# 1_V2.net
KiCad netlist of a schematic drawn in Altium Designer
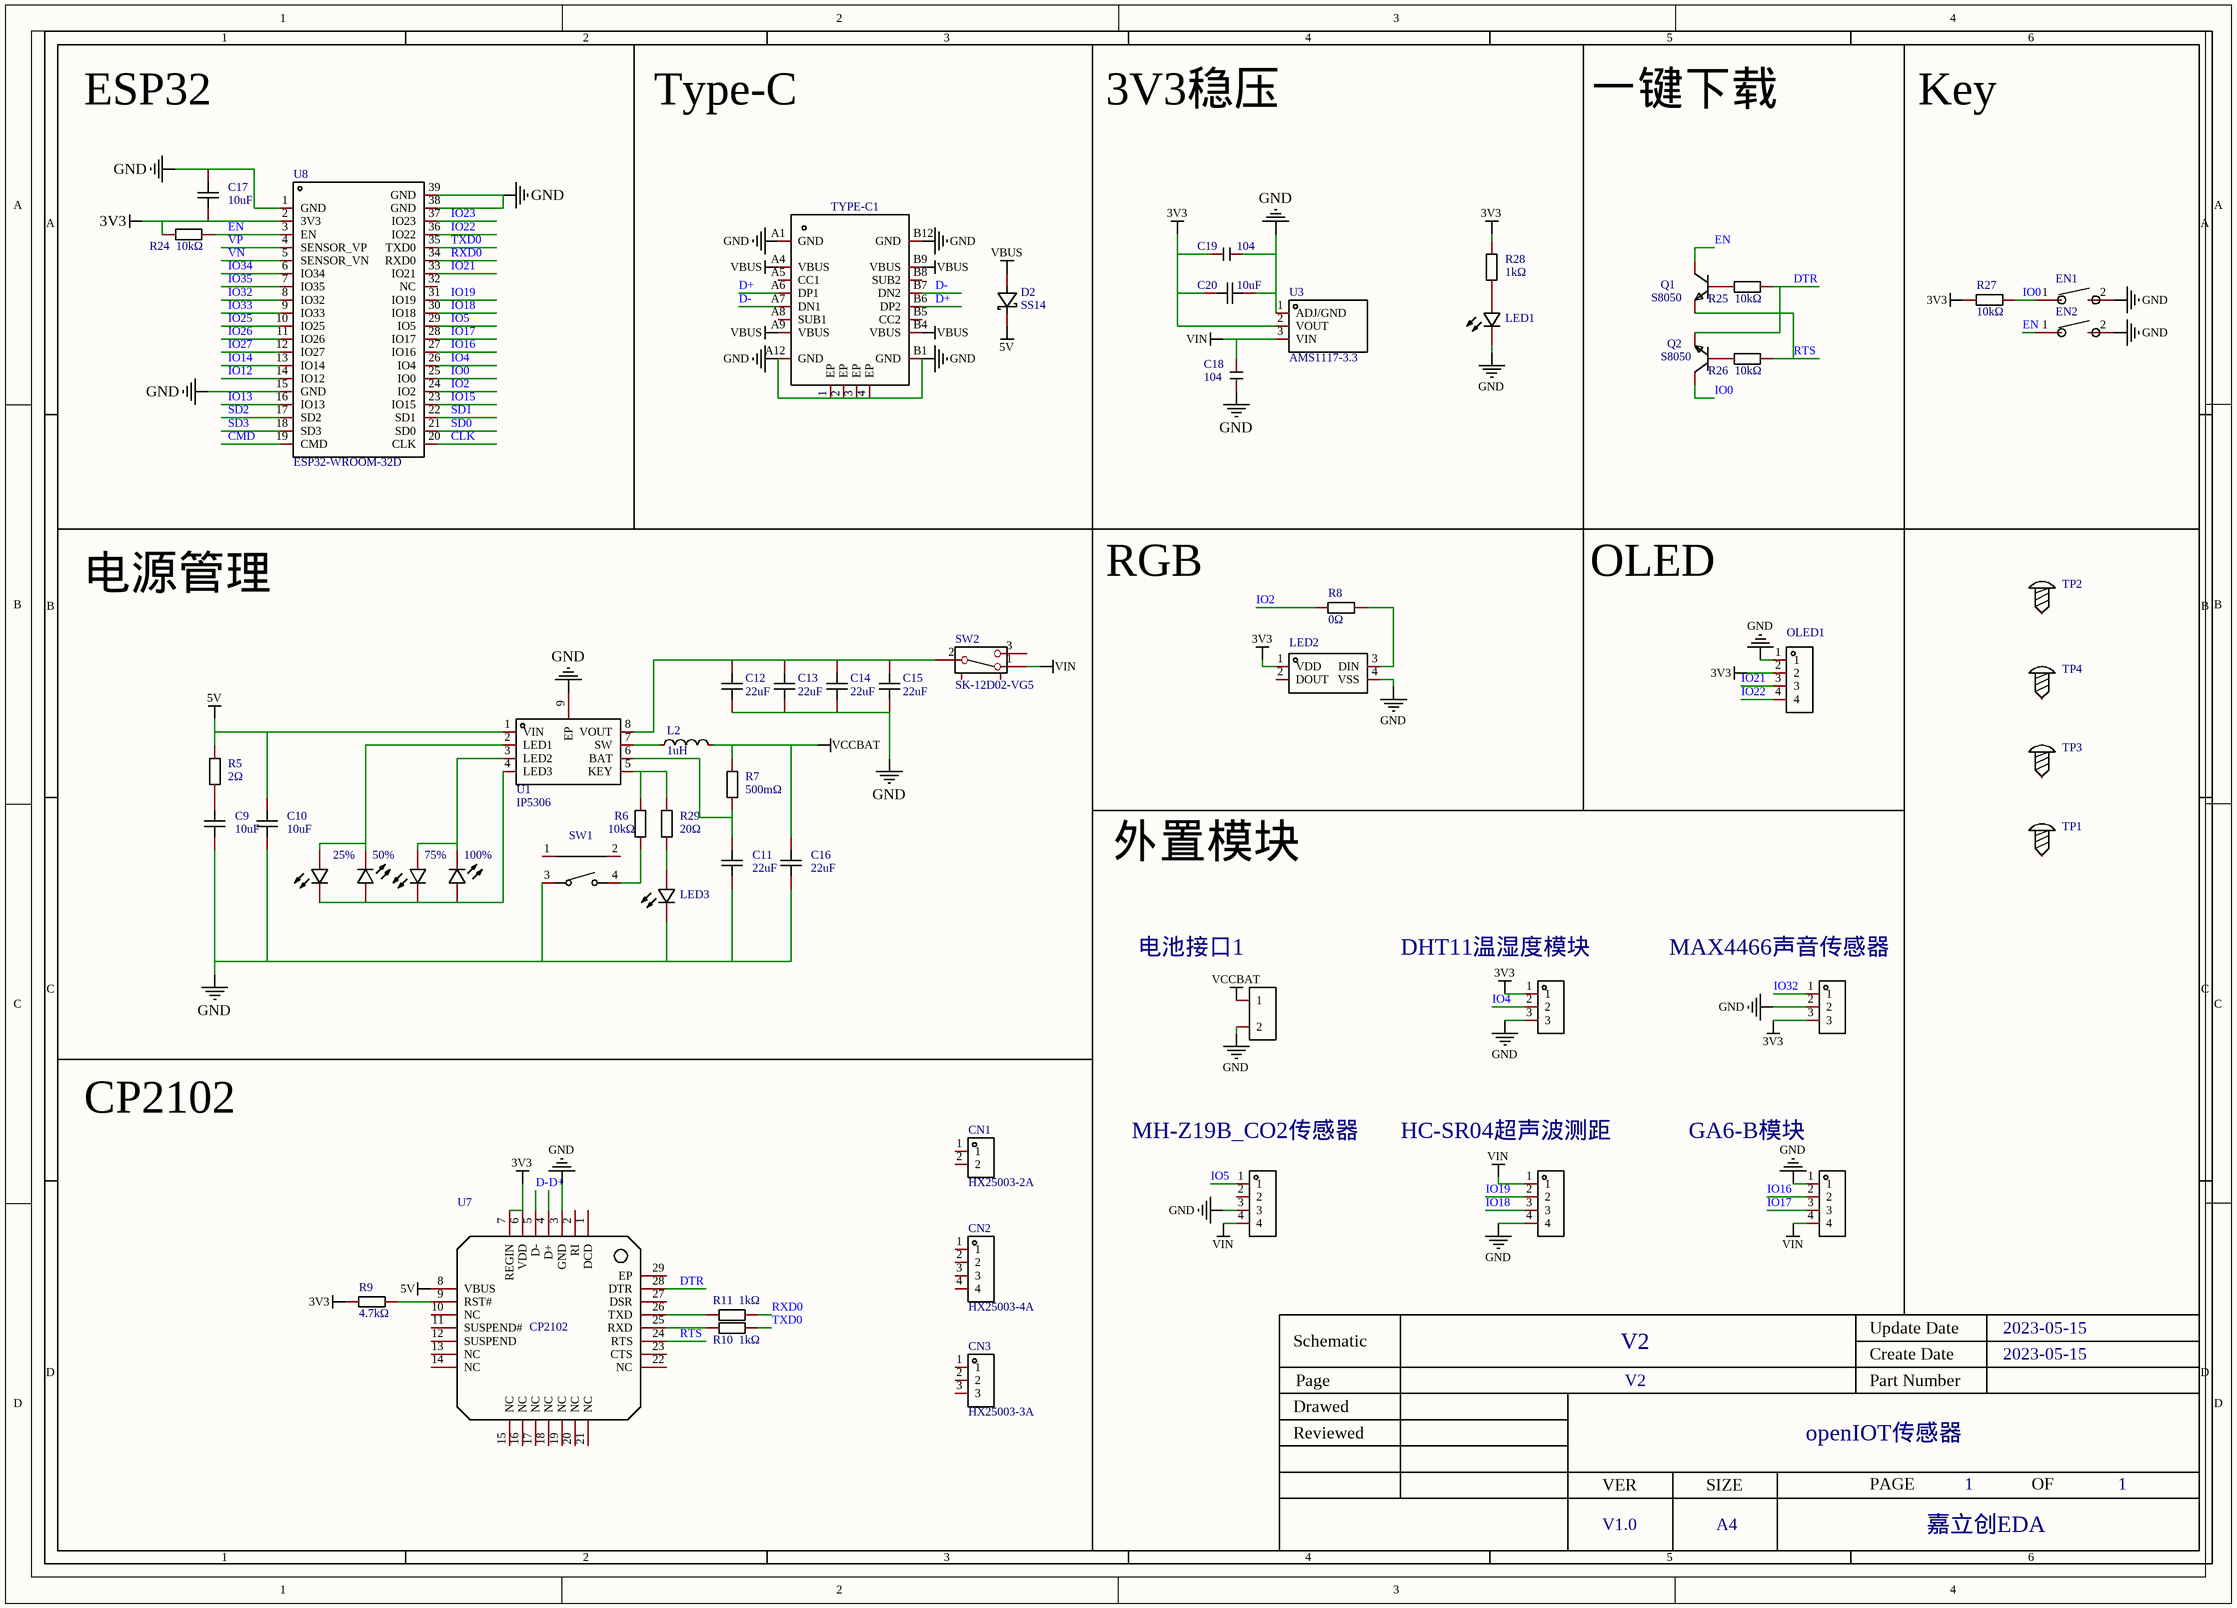
[diagram p0: 1_V2.schdoc]

(export (version "E")
  (design (tool "Eeschema 10.0.6"))
  (components
    (comp (ref "25%")
      (value "19-217/GHC-YR1S2/3T")
      (description "发光颜色:翠绿;二极管配置:-;主波长:520nm~535nm;色温:-;功率:110mW;安装方式:-;")
      (fields (field (name "MANUFACTURER") "EVERLIGHT(亿光)"))
      (libsource (lib "altium-import") (part "root_1_19-217/GHC-YR1S2/3T_"))
    )
    (comp (ref "50%")
      (value "19-217/GHC-YR1S2/3T")
      (description "发光颜色:翠绿;二极管配置:-;主波长:520nm~535nm;色温:-;功率:110mW;安装方式:-;")
      (fields (field (name "MANUFACTURER") "EVERLIGHT(亿光)"))
      (libsource (lib "altium-import") (part "root_3_19-217/GHC-YR1S2/3T_"))
    )
    (comp (ref "75%")
      (value "19-217/GHC-YR1S2/3T")
      (description "发光颜色:翠绿;二极管配置:-;主波长:520nm~535nm;色温:-;功率:110mW;安装方式:-;")
      (fields (field (name "MANUFACTURER") "EVERLIGHT(亿光)"))
      (libsource (lib "altium-import") (part "root_1_19-217/GHC-YR1S2/3T_"))
    )
    (comp (ref "100%")
      (value "19-217/GHC-YR1S2/3T")
      (description "发光颜色:翠绿;二极管配置:-;主波长:520nm~535nm;色温:-;功率:110mW;安装方式:-;")
      (fields (field (name "MANUFACTURER") "EVERLIGHT(亿光)"))
      (libsource (lib "altium-import") (part "root_3_19-217/GHC-YR1S2/3T_"))
    )
    (comp (ref "C9")
      (value "10uF")
      (description "容值:10uF;精度:±10%;额定电压:50V;材质(温度系数):X5R;")
      (fields
        (field (name "NAME") "10uF")
        (field (name "MANUFACTURER") "muRata(村田)")
        (field (name "MANUFACTURER PART") "GRM21BR61H106KE43L")
      )
      (libsource (lib "altium-import") (part "root_1_GRM21BR61H106KE43L_"))
    )
    (comp (ref "C10")
      (value "10uF")
      (description "容值:10uF;精度:±10%;额定电压:50V;材质(温度系数):X5R;")
      (fields
        (field (name "NAME") "10uF")
        (field (name "MANUFACTURER") "muRata(村田)")
        (field (name "MANUFACTURER PART") "GRM21BR61H106KE43L")
      )
      (libsource (lib "altium-import") (part "root_1_GRM21BR61H106KE43L_"))
    )
    (comp (ref "C11")
      (value "22uF")
      (description "容值:22uF;精度:±20%;额定电压:35V;材质(温度系数):X5R;")
      (fields
        (field (name "NAME") "22uF")
        (field (name "MANUFACTURER") "TDK")
        (field (name "MANUFACTURER PART") "C3216X5R1V226MTJ00E")
      )
      (libsource (lib "altium-import") (part "root_0_C3216X5R1V226MTJ00E_"))
    )
    (comp (ref "C12")
      (value "22uF")
      (description "容值:22uF;精度:±20%;额定电压:35V;材质(温度系数):X5R;")
      (fields
        (field (name "NAME") "22uF")
        (field (name "MANUFACTURER") "TDK")
        (field (name "MANUFACTURER PART") "C3216X5R1V226MTJ00E")
      )
      (libsource (lib "altium-import") (part "root_0_C3216X5R1V226MTJ00E_"))
    )
    (comp (ref "C13")
      (value "22uF")
      (description "容值:22uF;精度:±20%;额定电压:35V;材质(温度系数):X5R;")
      (fields
        (field (name "NAME") "22uF")
        (field (name "MANUFACTURER") "TDK")
        (field (name "MANUFACTURER PART") "C3216X5R1V226MTJ00E")
      )
      (libsource (lib "altium-import") (part "root_0_C3216X5R1V226MTJ00E_"))
    )
    (comp (ref "C14")
      (value "22uF")
      (description "容值:22uF;精度:±20%;额定电压:35V;材质(温度系数):X5R;")
      (fields
        (field (name "NAME") "22uF")
        (field (name "MANUFACTURER") "TDK")
        (field (name "MANUFACTURER PART") "C3216X5R1V226MTJ00E")
      )
      (libsource (lib "altium-import") (part "root_0_C3216X5R1V226MTJ00E_"))
    )
    (comp (ref "C15")
      (value "22uF")
      (description "容值:22uF;精度:±20%;额定电压:35V;材质(温度系数):X5R;")
      (fields
        (field (name "NAME") "22uF")
        (field (name "MANUFACTURER") "TDK")
        (field (name "MANUFACTURER PART") "C3216X5R1V226MTJ00E")
      )
      (libsource (lib "altium-import") (part "root_0_C3216X5R1V226MTJ00E_"))
    )
    (comp (ref "C16")
      (value "22uF")
      (description "容值:22uF;精度:±20%;额定电压:35V;材质(温度系数):X5R;")
      (fields
        (field (name "NAME") "22uF")
        (field (name "MANUFACTURER") "TDK")
        (field (name "MANUFACTURER PART") "C3216X5R1V226MTJ00E")
      )
      (libsource (lib "altium-import") (part "root_0_C3216X5R1V226MTJ00E_"))
    )
    (comp (ref "C17")
      (value "10uF")
      (description "容值:10uF;精度:±10%;额定电压:50V;材质(温度系数):X5R;")
      (fields
        (field (name "NAME") "10uF")
        (field (name "MANUFACTURER") "muRata(村田)")
        (field (name "MANUFACTURER PART") "GRM21BR61H106KE43L")
      )
      (libsource (lib "altium-import") (part "root_1_GRM21BR61H106KE43L_"))
    )
    (comp (ref "C18")
      (value "104")
      (fields (field (name "NAME") "104") (field (name "版权归属") "源创客"))
      (libsource (lib "altium-import") (part "root_1_104_"))
    )
    (comp (ref "C19")
      (value "104")
      (fields (field (name "NAME") "104") (field (name "版权归属") "源创客"))
      (libsource (lib "altium-import") (part "root_2_104_"))
    )
    (comp (ref "C20")
      (value "10uF")
      (description "容值:10uF;精度:±10%;额定电压:50V;材质(温度系数):X5R;")
      (fields
        (field (name "NAME") "10uF")
        (field (name "MANUFACTURER") "muRata(村田)")
        (field (name "MANUFACTURER PART") "GRM21BR61H106KE43L")
      )
      (libsource (lib "altium-import") (part "root_2_GRM21BR61H106KE43L_"))
    )
    (comp (ref "CN1")
      (value "HX25003-2A")
      (description "参考系列:XH;间距:2.5mm;插针结构:1x2P;排数:1;每排PIN数:2;行距:-;公母:公型插针;安装方式:直插;额定电流:-;工作温度范围:-;")
      (fields (field (name "NAME") "HX25003-2A") (field (name "MANUFACTURER") "HX(红星)"))
      (libsource (lib "altium-import") (part "root_0_HX25003-2A_"))
    )
    (comp (ref "CN2")
      (value "HX25003-4A")
      (description "参考系列:XH;间距:2.5mm;插针结构:1x4P;排数:1;每排PIN数:4;行距:-;公母:公型插针;安装方式:直插;额定电流:-;工作温度范围:-;")
      (fields (field (name "NAME") "HX25003-4A") (field (name "MANUFACTURER") "HX(红星)"))
      (libsource (lib "altium-import") (part "root_0_HX25003-4A_"))
    )
    (comp (ref "CN3")
      (value "HX25003-3A")
      (description "参考系列:XH;间距:2.5mm;插针结构:1x3P;排数:1;每排PIN数:3;行距:-;公母:公型插针;安装方式:直插;额定电流:-;工作温度范围:-;")
      (fields (field (name "NAME") "HX25003-3A") (field (name "MANUFACTURER") "HX(红星)"))
      (libsource (lib "altium-import") (part "root_0_HX25003-3A_"))
    )
    (comp (ref "D2")
      (value "SS14")
      (description "二极管配置:-;直流反向耐压(Vr):40V;平均整流电流(Io):1A;正向压降(Vf):550mV@1A;反向电流(Ir):500uA@40V;")
      (fields (field (name "NAME") "SS14") (field (name "MANUFACTURER") "KUU"))
      (libsource (lib "altium-import") (part "root_1_SS14_C2909920_"))
    )
    (comp (ref "DHT11温湿度模块")
      (value "B-2200S03P-A120")
      (description "排数:单排;总孔位数:3;间距:2.54mm;插孔结构:1x3P;行距:-;安装类型:直插;塑高:-;触头材质:黄铜;触头镀层:-;")
      (fields (field (name "MANUFACTURER") "Ckmtw(灿科盟)"))
      (libsource (lib "altium-import") (part "root_0_B-2200S03P-A120_"))
    )
    (comp (ref "EN1")
      (value "TSA343G00-250J2")
      (fields (field (name "MANUFACTURER") "BRIGHT(博瑞泰)"))
      (libsource (lib "altium-import") (part "root_0_TSA343G00-250J2_"))
    )
    (comp (ref "EN2")
      (value "TSA343G00-250J2")
      (fields (field (name "MANUFACTURER") "BRIGHT(博瑞泰)"))
      (libsource (lib "altium-import") (part "root_0_TSA343G00-250J2_"))
    )
    (comp (ref "GA6-B模块")
      (value "2.54-1*4P母")
      (fields (field (name "MANUFACTURER") "BOOMELE(博穆精密)"))
      (libsource (lib "altium-import") (part "root_0_2.54-1*4P母_"))
    )
    (comp (ref "HC-SR04超声波测距")
      (value "2.54-1*4P母")
      (fields (field (name "MANUFACTURER") "BOOMELE(博穆精密)"))
      (libsource (lib "altium-import") (part "root_0_2.54-1*4P母_"))
    )
    (comp (ref "L2")
      (value "1uH")
      (description "电感值:1uH;精度:±20%;额定电流:8.5A;饱和电流(Isat):14A;")
      (fields
        (field (name "NAME") "1uH")
        (field (name "MANUFACTURER") "cjiang(长江微电)")
        (field (name "MANUFACTURER PART") "FXL0618-1R0-M")
      )
      (libsource (lib "altium-import") (part "root_0_FXL0618-1R0-M_"))
    )
    (comp (ref "LED1")
      (value "19-217/GHC-YR1S2/3T")
      (description "发光颜色:翠绿;二极管配置:-;主波长:520nm~535nm;色温:-;功率:110mW;安装方式:-;")
      (fields (field (name "MANUFACTURER") "EVERLIGHT(亿光)"))
      (libsource (lib "altium-import") (part "root_1_19-217/GHC-YR1S2/3T_"))
    )
    (comp (ref "LED2")
      (value "WS2812B-V5/W")
      (fields (field (name "MANUFACTURER") "worldsemi"))
      (libsource (lib "altium-import") (part "root_0_WS2812B-V5/W_"))
    )
    (comp (ref "LED3")
      (value "19-217/GHC-YR1S2/3T")
      (description "发光颜色:翠绿;二极管配置:-;主波长:520nm~535nm;色温:-;功率:110mW;安装方式:-;")
      (fields (field (name "MANUFACTURER") "EVERLIGHT(亿光)"))
      (libsource (lib "altium-import") (part "root_1_19-217/GHC-YR1S2/3T_"))
    )
    (comp (ref "MAX4466声音传感器")
      (value "B-2200S03P-A120")
      (description "排数:单排;总孔位数:3;间距:2.54mm;插孔结构:1x3P;行距:-;安装类型:直插;塑高:-;触头材质:黄铜;触头镀层:-;")
      (fields (field (name "MANUFACTURER") "Ckmtw(灿科盟)"))
      (libsource (lib "altium-import") (part "root_0_B-2200S03P-A120_"))
    )
    (comp (ref "MH-Z19B_CO2传感器")
      (value "2.54-1*4P母")
      (fields (field (name "MANUFACTURER") "BOOMELE(博穆精密)"))
      (libsource (lib "altium-import") (part "root_0_2.54-1*4P母_"))
    )
    (comp (ref "OLED1")
      (value "2.54-1*4P母")
      (fields (field (name "MANUFACTURER") "BOOMELE(博穆精密)"))
      (libsource (lib "altium-import") (part "root_0_2.54-1*4P母_"))
    )
    (comp (ref "Q1")
      (value "S8050")
      (fields (field (name "NAME") "S8050") (field (name "MANUFACTURER") "WPMtek(维攀微)"))
      (libsource (lib "altium-import") (part "root_0_S8050_"))
    )
    (comp (ref "Q2")
      (value "S8050")
      (fields (field (name "NAME") "S8050") (field (name "MANUFACTURER") "WPMtek(维攀微)"))
      (libsource (lib "altium-import") (part "root_2_S8050_"))
    )
    (comp (ref "R5")
      (value "2Ω")
      (description "电阻类型:厚膜电阻;阻值:2Ω;精度:±1%;功率:125mW;")
      (fields
        (field (name "NAME") "2Ω")
        (field (name "MANUFACTURER") "UNI-ROYAL(厚声)")
        (field (name "MANUFACTURER PART") "0805W8F200KT5E")
      )
      (libsource (lib "altium-import") (part "root_1_0805W8F200KT5E_"))
    )
    (comp (ref "R6")
      (value "10kΩ")
      (description "电阻类型:厚膜电阻;阻值:10kΩ;精度:±1%;功率:125mW;")
      (fields
        (field (name "NAME") "10kΩ")
        (field (name "MANUFACTURER") "UNI-ROYAL(厚声)")
        (field (name "MANUFACTURER PART") "0805W8F1002T5E")
      )
      (libsource (lib "altium-import") (part "root_1_0805W8F1002T5E_C17414_"))
    )
    (comp (ref "R7")
      (value "500mΩ")
      (description "电阻类型:厚膜电阻;阻值:500mΩ;精度:±1%;功率:250mW;")
      (fields
        (field (name "NAME") "500mΩ")
        (field (name "MANUFACTURER") "UNI-ROYAL(厚声)")
        (field (name "MANUFACTURER PART") "1206W4F500LT5E")
      )
      (libsource (lib "altium-import") (part "root_1_1206W4F500LT5E_"))
    )
    (comp (ref "R8")
      (value "0Ω")
      (description "电阻类型:厚膜电阻;阻值:0Ω;精度:±1%;功率:100mW;最大工作电压:75V;工作温度范围:-55℃~+155℃;")
      (fields
        (field (name "MANUFACTURER") "UNI-ROYAL(厚声)")
        (field (name "MANUFACTURER PART") "0603WAF0000T5E")
      )
      (libsource (lib "altium-import") (part "root_2_0603WAF0000T5E_"))
    )
    (comp (ref "R9")
      (value "4.7kΩ")
      (description "电阻类型:厚膜电阻;阻值:4.7kΩ;精度:±1%;功率:100mW;")
      (fields
        (field (name "NAME") "4.7kΩ")
        (field (name "MANUFACTURER") "UNI-ROYAL(厚声)")
        (field (name "MANUFACTURER PART") "0603WAF4701T5E")
      )
      (libsource (lib "altium-import") (part "root_0_0603WAF4701T5E_"))
    )
    (comp (ref "R10")
      (value "1kΩ")
      (description "电阻类型:厚膜电阻;阻值:1kΩ;精度:±1%;功率:100mW;")
      (fields
        (field (name "NAME") "1kΩ")
        (field (name "MANUFACTURER") "UNI-ROYAL(厚声)")
        (field (name "MANUFACTURER PART") "0603WAF1001T5E")
      )
      (libsource (lib "altium-import") (part "root_0_0603WAF1001T5E_"))
    )
    (comp (ref "R11")
      (value "1kΩ")
      (description "电阻类型:厚膜电阻;阻值:1kΩ;精度:±1%;功率:100mW;")
      (fields
        (field (name "NAME") "1kΩ")
        (field (name "MANUFACTURER") "UNI-ROYAL(厚声)")
        (field (name "MANUFACTURER PART") "0603WAF1001T5E")
      )
      (libsource (lib "altium-import") (part "root_0_0603WAF1001T5E_"))
    )
    (comp (ref "R24")
      (value "10kΩ")
      (description "电阻类型:厚膜电阻;阻值:10kΩ;精度:±1%;功率:100mW;")
      (fields
        (field (name "NAME") "10kΩ")
        (field (name "MANUFACTURER") "UNI-ROYAL(厚声)")
        (field (name "MANUFACTURER PART") "0603WAF1002T5E")
      )
      (libsource (lib "altium-import") (part "root_0_0603WAF1002T5E_"))
    )
    (comp (ref "R25")
      (value "10kΩ")
      (description "电阻类型:厚膜电阻;阻值:10kΩ;精度:±1%;功率:100mW;")
      (fields
        (field (name "NAME") "10kΩ")
        (field (name "MANUFACTURER") "UNI-ROYAL(厚声)")
        (field (name "MANUFACTURER PART") "0603WAF1002T5E")
      )
      (libsource (lib "altium-import") (part "root_0_0603WAF1002T5E_"))
    )
    (comp (ref "R26")
      (value "10kΩ")
      (description "电阻类型:厚膜电阻;阻值:10kΩ;精度:±1%;功率:100mW;")
      (fields
        (field (name "NAME") "10kΩ")
        (field (name "MANUFACTURER") "UNI-ROYAL(厚声)")
        (field (name "MANUFACTURER PART") "0603WAF1002T5E")
      )
      (libsource (lib "altium-import") (part "root_0_0603WAF1002T5E_"))
    )
    (comp (ref "R27")
      (value "10kΩ")
      (description "电阻类型:厚膜电阻;阻值:10kΩ;精度:±1%;功率:100mW;")
      (fields
        (field (name "NAME") "10kΩ")
        (field (name "MANUFACTURER") "UNI-ROYAL(厚声)")
        (field (name "MANUFACTURER PART") "0603WAF1002T5E")
      )
      (libsource (lib "altium-import") (part "root_2_0603WAF1002T5E_"))
    )
    (comp (ref "R28")
      (value "1kΩ")
      (description "电阻类型:厚膜电阻;阻值:1kΩ;精度:±1%;功率:100mW;")
      (fields
        (field (name "NAME") "1kΩ")
        (field (name "MANUFACTURER") "UNI-ROYAL(厚声)")
        (field (name "MANUFACTURER PART") "0603WAF1001T5E")
      )
      (libsource (lib "altium-import") (part "root_1_0603WAF1001T5E_"))
    )
    (comp (ref "R29")
      (value "20Ω")
      (description "电阻类型:厚膜电阻;阻值:20Ω;精度:±1%;功率:100mW;")
      (fields
        (field (name "NAME") "20Ω")
        (field (name "MANUFACTURER") "UNI-ROYAL(厚声)")
        (field (name "MANUFACTURER PART") "0603WAF200JT5E")
      )
      (libsource (lib "altium-import") (part "root_1_0603WAF200JT5E_"))
    )
    (comp (ref "SW1")
      (value "TS24CA")
      (description "触点电流:50mA;额定电压(DC):12V;电路结构:单刀单掷;安装方式:卧贴;带灯:-;机械寿命:-;")
      (fields (field (name "MANUFACTURER") "SHOU HAN(首韩)"))
      (libsource (lib "altium-import") (part "root_0_TS24CA_"))
    )
    (comp (ref "SW2")
      (value "SK-12D02-VG5")
      (fields (field (name "NAME") "SK-12D02-VG5") (field (name "MANUFACTURER") "韩国韩荣"))
      (libsource (lib "altium-import") (part "root_0_SK-12D02-VG5_C136722_"))
    )
    (comp (ref "TP1") (value "M2螺丝") (libsource (lib "altium-import") (part "root_0_M2螺丝_")))
    (comp (ref "TP2") (value "M2螺丝") (libsource (lib "altium-import") (part "root_0_M2螺丝_")))
    (comp (ref "TP3") (value "M2螺丝") (libsource (lib "altium-import") (part "root_0_M2螺丝_")))
    (comp (ref "TP4") (value "M2螺丝") (libsource (lib "altium-import") (part "root_0_M2螺丝_")))
    (comp (ref "TYPE-C1")
      (value "KH-TYPE-C-16P")
      (description "连接器类型:Type-C;标准:-;公母:母座;触点数量:16;端口数量:1;安装方式:卧贴;额定电流 - 电源:3A;工作温度范围:-40℃~+85℃;")
      (fields (field (name "MANUFACTURER") "kinghelm(金航标)"))
      (libsource (lib "altium-import") (part "root_0_KH-TYPE-C-16P_"))
    )
    (comp (ref "U1")
      (value "IP5306")
      (description "2.1A充电2.4A放电高集成度移动电源SOC")
      (fields (field (name "NAME") "IP5306") (field (name "MANUFACTURER") "INJOINIC(英集芯)"))
      (libsource (lib "altium-import") (part "root_0_IP5306_"))
    )
    (comp (ref "U3")
      (value "AMS1117-3.3")
      (description "输出类型:-;")
      (fields (field (name "NAME") "AMS1117-3.3") (field (name "MANUFACTURER") "Slkor(萨科微)"))
      (libsource (lib "altium-import") (part "root_0_AMS1117-3.3_C880752_"))
    )
    (comp (ref "U7")
      (value "CP2102")
      (description "类型:Transceiver;协议类别:USB;驱动器/接收器数:1/1;数据速率:1Mbps;")
      (fields (field (name "NAME") "CP2102") (field (name "MANUFACTURER") "SILICON LABS(芯科)"))
      (libsource (lib "altium-import") (part "root_3_CP2102-GMR_"))
    )
    (comp (ref "U8")
      (value "ESP32-WROOM-32D")
      (fields (field (name "NAME") "ESP32-WROOM-32D"))
      (libsource (lib "altium-import") (part "root_0_ESP32-WROOM-32D_"))
    )
    (comp (ref "电池接口1")
      (value "826629-2")
      (fields (field (name "MANUFACTURER") "TE Connectivity(美国泰科)"))
      (libsource (lib "altium-import") (part "root_0_826629-2_"))
    )
  )
  (nets
    (net (code "1") (name "/CLK") (class "Default")
      (node (ref "U8") (pin "20") (pinfunction "CLK_20") (pintype "passive"))
    )
    (net (code "2") (name "/CMD") (class "Default")
      (node (ref "U8") (pin "19") (pinfunction "CMD_19") (pintype "passive"))
    )
    (net (code "3") (name "/D+") (class "Default")
      (node (ref "TYPE-C1") (pin "A6") (pinfunction "DP1_A6") (pintype "passive"))
      (node (ref "TYPE-C1") (pin "B6") (pinfunction "DP2_B6") (pintype "passive"))
      (node (ref "U7") (pin "4") (pinfunction "D+_4") (pintype "passive"))
    )
    (net (code "4") (name "/D-") (class "Default")
      (node (ref "TYPE-C1") (pin "A7") (pinfunction "DN1_A7") (pintype "passive"))
      (node (ref "TYPE-C1") (pin "B7") (pinfunction "DN2_B7") (pintype "passive"))
      (node (ref "U7") (pin "5") (pinfunction "D-_5") (pintype "passive"))
    )
    (net (code "5") (name "/DTR") (class "Default")
      (node (ref "Q2") (pin "2") (pinfunction "E_2") (pintype "passive"))
      (node (ref "R25") (pin "2") (pinfunction "2_2") (pintype "passive"))
      (node (ref "U7") (pin "28") (pinfunction "DTR_28") (pintype "passive"))
    )
    (net (code "6") (name "/EN") (class "Default")
      (node (ref "EN2") (pin "1") (pinfunction "1_1") (pintype "passive"))
      (node (ref "Q1") (pin "3") (pinfunction "C_3") (pintype "passive"))
      (node (ref "R24") (pin "2") (pinfunction "2_2") (pintype "passive"))
      (node (ref "U8") (pin "3") (pinfunction "EN_3") (pintype "passive"))
    )
    (net (code "7") (name "/IO0") (class "Default")
      (node (ref "EN1") (pin "1") (pinfunction "1_1") (pintype "passive"))
      (node (ref "Q2") (pin "3") (pinfunction "C_3") (pintype "passive"))
      (node (ref "R27") (pin "1") (pinfunction "1_1") (pintype "passive"))
      (node (ref "U8") (pin "25") (pinfunction "IO0_25") (pintype "passive"))
    )
    (net (code "8") (name "/IO2") (class "Default")
      (node (ref "R8") (pin "2") (pinfunction "2_2") (pintype "passive"))
      (node (ref "U8") (pin "24") (pinfunction "IO2_24") (pintype "passive"))
    )
    (net (code "9") (name "/IO4") (class "Default")
      (node (ref "DHT11温湿度模块") (pin "2") (pinfunction "2_2") (pintype "passive"))
      (node (ref "U8") (pin "26") (pinfunction "IO4_26") (pintype "passive"))
    )
    (net (code "10") (name "/IO5") (class "Default")
      (node (ref "MH-Z19B_CO2传感器") (pin "1") (pinfunction "1_1") (pintype "passive"))
      (node (ref "U8") (pin "29") (pinfunction "IO5_29") (pintype "passive"))
    )
    (net (code "11") (name "/IO12") (class "Default")
      (node (ref "U8") (pin "14") (pinfunction "IO12_14") (pintype "passive"))
    )
    (net (code "12") (name "/IO13") (class "Default")
      (node (ref "U8") (pin "16") (pinfunction "IO13_16") (pintype "passive"))
    )
    (net (code "13") (name "/IO14") (class "Default")
      (node (ref "U8") (pin "13") (pinfunction "IO14_13") (pintype "passive"))
    )
    (net (code "14") (name "/IO15") (class "Default")
      (node (ref "U8") (pin "23") (pinfunction "IO15_23") (pintype "passive"))
    )
    (net (code "15") (name "/IO16") (class "Default")
      (node (ref "GA6-B模块") (pin "2") (pinfunction "2_2") (pintype "passive"))
      (node (ref "U8") (pin "27") (pinfunction "IO16_27") (pintype "passive"))
    )
    (net (code "16") (name "/IO17") (class "Default")
      (node (ref "GA6-B模块") (pin "3") (pinfunction "3_3") (pintype "passive"))
      (node (ref "U8") (pin "28") (pinfunction "IO17_28") (pintype "passive"))
    )
    (net (code "17") (name "/IO18") (class "Default")
      (node (ref "HC-SR04超声波测距") (pin "3") (pinfunction "3_3") (pintype "passive"))
      (node (ref "U8") (pin "30") (pinfunction "IO18_30") (pintype "passive"))
    )
    (net (code "18") (name "/IO19") (class "Default")
      (node (ref "HC-SR04超声波测距") (pin "2") (pinfunction "2_2") (pintype "passive"))
      (node (ref "U8") (pin "31") (pinfunction "IO19_31") (pintype "passive"))
    )
    (net (code "19") (name "/IO21") (class "Default")
      (node (ref "OLED1") (pin "3") (pinfunction "3_3") (pintype "passive"))
      (node (ref "U8") (pin "33") (pinfunction "IO21_33") (pintype "passive"))
    )
    (net (code "20") (name "/IO22") (class "Default")
      (node (ref "OLED1") (pin "4") (pinfunction "4_4") (pintype "passive"))
      (node (ref "U8") (pin "36") (pinfunction "IO22_36") (pintype "passive"))
    )
    (net (code "21") (name "/IO23") (class "Default")
      (node (ref "U8") (pin "37") (pinfunction "IO23_37") (pintype "passive"))
    )
    (net (code "22") (name "/IO25") (class "Default")
      (node (ref "U8") (pin "10") (pinfunction "IO25_10") (pintype "passive"))
    )
    (net (code "23") (name "/IO26") (class "Default")
      (node (ref "U8") (pin "11") (pinfunction "IO26_11") (pintype "passive"))
    )
    (net (code "24") (name "/IO27") (class "Default")
      (node (ref "U8") (pin "12") (pinfunction "IO27_12") (pintype "passive"))
    )
    (net (code "25") (name "/IO32") (class "Default")
      (node (ref "MAX4466声音传感器") (pin "1") (pinfunction "1_1") (pintype "passive"))
      (node (ref "U8") (pin "8") (pinfunction "IO32_8") (pintype "passive"))
    )
    (net (code "26") (name "/IO33") (class "Default")
      (node (ref "U8") (pin "9") (pinfunction "IO33_9") (pintype "passive"))
    )
    (net (code "27") (name "/IO34") (class "Default")
      (node (ref "U8") (pin "6") (pinfunction "IO34_6") (pintype "passive"))
    )
    (net (code "28") (name "/IO35") (class "Default")
      (node (ref "U8") (pin "7") (pinfunction "IO35_7") (pintype "passive"))
    )
    (net (code "29") (name "/RTS") (class "Default")
      (node (ref "Q1") (pin "2") (pinfunction "E_2") (pintype "passive"))
      (node (ref "R26") (pin "2") (pinfunction "2_2") (pintype "passive"))
      (node (ref "U7") (pin "24") (pinfunction "RTS_24") (pintype "passive"))
    )
    (net (code "30") (name "/RXD0") (class "Default")
      (node (ref "R11") (pin "2") (pinfunction "2_2") (pintype "passive"))
      (node (ref "U8") (pin "34") (pinfunction "RXD0_34") (pintype "passive"))
    )
    (net (code "31") (name "/SD0") (class "Default")
      (node (ref "U8") (pin "21") (pinfunction "SD0_21") (pintype "passive"))
    )
    (net (code "32") (name "/SD1") (class "Default")
      (node (ref "U8") (pin "22") (pinfunction "SD1_22") (pintype "passive"))
    )
    (net (code "33") (name "/SD2") (class "Default")
      (node (ref "U8") (pin "17") (pinfunction "SD2_17") (pintype "passive"))
    )
    (net (code "34") (name "/SD3") (class "Default")
      (node (ref "U8") (pin "18") (pinfunction "SD3_18") (pintype "passive"))
    )
    (net (code "35") (name "/TXD0") (class "Default")
      (node (ref "R10") (pin "2") (pinfunction "2_2") (pintype "passive"))
      (node (ref "U8") (pin "35") (pinfunction "TXD0_35") (pintype "passive"))
    )
    (net (code "36") (name "/VN") (class "Default")
      (node (ref "U8") (pin "5") (pinfunction "SENSOR_VN_5") (pintype "passive"))
    )
    (net (code "37") (name "/VP") (class "Default")
      (node (ref "U8") (pin "4") (pinfunction "SENSOR_VP_4") (pintype "passive"))
    )
    (net (code "38") (name "3V3") (class "Default")
      (node (ref "C17") (pin "1") (pinfunction "1_1") (pintype "passive"))
      (node (ref "C19") (pin "2") (pinfunction "2_2") (pintype "passive"))
      (node (ref "C20") (pin "2") (pinfunction "2_2") (pintype "passive"))
      (node (ref "DHT11温湿度模块") (pin "1") (pinfunction "1_1") (pintype "passive"))
      (node (ref "LED2") (pin "1") (pinfunction "VDD_1") (pintype "passive"))
      (node (ref "MAX4466声音传感器") (pin "3") (pinfunction "3_3") (pintype "passive"))
      (node (ref "OLED1") (pin "2") (pinfunction "2_2") (pintype "passive"))
      (node (ref "R24") (pin "1") (pinfunction "1_1") (pintype "passive"))
      (node (ref "R27") (pin "2") (pinfunction "2_2") (pintype "passive"))
      (node (ref "R28") (pin "2") (pinfunction "2_2") (pintype "passive"))
      (node (ref "R9") (pin "1") (pinfunction "1_1") (pintype "passive"))
      (node (ref "U3") (pin "2") (pinfunction "VOUT_2") (pintype "passive"))
      (node (ref "U7") (pin "6") (pinfunction "VDD_6") (pintype "passive"))
      (node (ref "U7") (pin "7") (pinfunction "REGIN_7") (pintype "passive"))
      (node (ref "U8") (pin "2") (pinfunction "3V3_2") (pintype "passive"))
    )
    (net (code "39") (name "5V") (class "Default")
      (node (ref "C10") (pin "2") (pinfunction "2_2") (pintype "passive"))
      (node (ref "D2") (pin "1") (pinfunction "A_1") (pintype "passive"))
      (node (ref "R5") (pin "2") (pinfunction "2_2") (pintype "passive"))
      (node (ref "U1") (pin "1") (pinfunction "VIN_1") (pintype "passive"))
      (node (ref "U7") (pin "8") (pinfunction "VBUS_8") (pintype "passive"))
    )
    (net (code "40") (name "GND") (class "Default")
      (node (ref "C10") (pin "1") (pinfunction "1_1") (pintype "passive"))
      (node (ref "C11") (pin "1") (pinfunction "1_1") (pintype "passive"))
      (node (ref "C12") (pin "1") (pinfunction "1_1") (pintype "passive"))
      (node (ref "C13") (pin "1") (pinfunction "1_1") (pintype "passive"))
      (node (ref "C14") (pin "1") (pinfunction "1_1") (pintype "passive"))
      (node (ref "C15") (pin "1") (pinfunction "1_1") (pintype "passive"))
      (node (ref "C16") (pin "1") (pinfunction "1_1") (pintype "passive"))
      (node (ref "C17") (pin "2") (pinfunction "2_2") (pintype "passive"))
      (node (ref "C18") (pin "1") (pinfunction "1_1") (pintype "passive"))
      (node (ref "C19") (pin "1") (pinfunction "1_1") (pintype "passive"))
      (node (ref "C20") (pin "1") (pinfunction "1_1") (pintype "passive"))
      (node (ref "C9") (pin "1") (pinfunction "1_1") (pintype "passive"))
      (node (ref "DHT11温湿度模块") (pin "3") (pinfunction "3_3") (pintype "passive"))
      (node (ref "EN1") (pin "2") (pinfunction "2_2") (pintype "passive"))
      (node (ref "EN2") (pin "2") (pinfunction "2_2") (pintype "passive"))
      (node (ref "GA6-B模块") (pin "1") (pinfunction "1_1") (pintype "passive"))
      (node (ref "HC-SR04超声波测距") (pin "4") (pinfunction "4_4") (pintype "passive"))
      (node (ref "LED1") (pin "1") (pinfunction "C_1") (pintype "passive"))
      (node (ref "LED2") (pin "4") (pinfunction "VSS_4") (pintype "passive"))
      (node (ref "LED3") (pin "1") (pinfunction "C_1") (pintype "passive"))
      (node (ref "MAX4466声音传感器") (pin "2") (pinfunction "2_2") (pintype "passive"))
      (node (ref "MH-Z19B_CO2传感器") (pin "3") (pinfunction "3_3") (pintype "passive"))
      (node (ref "OLED1") (pin "1") (pinfunction "1_1") (pintype "passive"))
      (node (ref "SW1") (pin "3") (pinfunction "3_3") (pintype "passive"))
      (node (ref "TYPE-C1") (pin "1") (pinfunction "EP_1") (pintype "passive"))
      (node (ref "TYPE-C1") (pin "2") (pinfunction "EP_2") (pintype "passive"))
      (node (ref "TYPE-C1") (pin "3") (pinfunction "EP_3") (pintype "passive"))
      (node (ref "TYPE-C1") (pin "4") (pinfunction "EP_4") (pintype "passive"))
      (node (ref "TYPE-C1") (pin "A1") (pinfunction "GND_A1") (pintype "passive"))
      (node (ref "TYPE-C1") (pin "A12") (pinfunction "GND_A12") (pintype "passive"))
      (node (ref "TYPE-C1") (pin "B1") (pinfunction "GND_B1") (pintype "passive"))
      (node (ref "TYPE-C1") (pin "B12") (pinfunction "GND_B12") (pintype "passive"))
      (node (ref "U1") (pin "9") (pinfunction "EP_9") (pintype "passive"))
      (node (ref "U3") (pin "1") (pinfunction "ADJ/GND_1") (pintype "passive"))
      (node (ref "U7") (pin "3") (pinfunction "GND_3") (pintype "passive"))
      (node (ref "U8") (pin "1") (pinfunction "GND_1") (pintype "passive"))
      (node (ref "U8") (pin "15") (pinfunction "GND_15") (pintype "passive"))
      (node (ref "U8") (pin "38") (pinfunction "GND_38") (pintype "passive"))
      (node (ref "U8") (pin "39") (pinfunction "GND_39") (pintype "passive"))
      (node (ref "电池接口1") (pin "2") (pinfunction "2_2") (pintype "passive"))
    )
    (net (code "41") (name "Net-(25%-A)") (class "Default")
      (node (ref "25%") (pin "2") (pinfunction "A_2") (pintype "passive"))
      (node (ref "50%") (pin "1") (pinfunction "C_1") (pintype "passive"))
      (node (ref "U1") (pin "2") (pinfunction "LED1_2") (pintype "passive"))
    )
    (net (code "42") (name "Net-(100%-A)") (class "Default")
      (node (ref "100%") (pin "2") (pinfunction "A_2") (pintype "passive"))
      (node (ref "25%") (pin "1") (pinfunction "C_1") (pintype "passive"))
      (node (ref "50%") (pin "2") (pinfunction "A_2") (pintype "passive"))
      (node (ref "75%") (pin "1") (pinfunction "C_1") (pintype "passive"))
      (node (ref "U1") (pin "4") (pinfunction "LED3_4") (pintype "passive"))
    )
    (net (code "43") (name "Net-(100%-C)") (class "Default")
      (node (ref "100%") (pin "1") (pinfunction "C_1") (pintype "passive"))
      (node (ref "75%") (pin "2") (pinfunction "A_2") (pintype "passive"))
      (node (ref "U1") (pin "3") (pinfunction "LED2_3") (pintype "passive"))
    )
    (net (code "44") (name "Net-(C9-Pad2)") (class "Default")
      (node (ref "C9") (pin "2") (pinfunction "2_2") (pintype "passive"))
      (node (ref "R5") (pin "1") (pinfunction "1_1") (pintype "passive"))
    )
    (net (code "45") (name "Net-(LED1-A)") (class "Default")
      (node (ref "LED1") (pin "2") (pinfunction "A_2") (pintype "passive"))
      (node (ref "R28") (pin "1") (pinfunction "1_1") (pintype "passive"))
    )
    (net (code "46") (name "Net-(LED2-DIN)") (class "Default")
      (node (ref "LED2") (pin "3") (pinfunction "DIN_3") (pintype "passive"))
      (node (ref "R8") (pin "1") (pinfunction "1_1") (pintype "passive"))
    )
    (net (code "47") (name "Net-(LED3-A)") (class "Default")
      (node (ref "LED3") (pin "2") (pinfunction "A_2") (pintype "passive"))
      (node (ref "R29") (pin "1") (pinfunction "1_1") (pintype "passive"))
    )
    (net (code "48") (name "Net-(Q1-B)") (class "Default")
      (node (ref "Q1") (pin "1") (pinfunction "B_1") (pintype "passive"))
      (node (ref "R25") (pin "1") (pinfunction "1_1") (pintype "passive"))
    )
    (net (code "49") (name "Net-(Q2-B)") (class "Default")
      (node (ref "Q2") (pin "1") (pinfunction "B_1") (pintype "passive"))
      (node (ref "R26") (pin "1") (pinfunction "1_1") (pintype "passive"))
    )
    (net (code "50") (name "Net-(R6-Pad1)") (class "Default")
      (node (ref "R6") (pin "1") (pinfunction "1_1") (pintype "passive"))
      (node (ref "SW1") (pin "4") (pinfunction "4_4") (pintype "passive"))
    )
    (net (code "51") (name "Net-(U1-BAT)") (class "Default")
      (node (ref "C11") (pin "2") (pinfunction "2_2") (pintype "passive"))
      (node (ref "R7") (pin "1") (pinfunction "1_1") (pintype "passive"))
      (node (ref "U1") (pin "6") (pinfunction "BAT_6") (pintype "passive"))
    )
    (net (code "52") (name "Net-(U1-KEY)") (class "Default")
      (node (ref "R29") (pin "2") (pinfunction "2_2") (pintype "passive"))
      (node (ref "R6") (pin "2") (pinfunction "2_2") (pintype "passive"))
      (node (ref "U1") (pin "5") (pinfunction "KEY_5") (pintype "passive"))
    )
    (net (code "53") (name "Net-(U1-SW)") (class "Default")
      (node (ref "L2") (pin "1") (pinfunction "1_1") (pintype "passive"))
      (node (ref "U1") (pin "7") (pinfunction "SW_7") (pintype "passive"))
    )
    (net (code "54") (name "Net-(U1-VOUT)") (class "Default")
      (node (ref "C12") (pin "2") (pinfunction "2_2") (pintype "passive"))
      (node (ref "C13") (pin "2") (pinfunction "2_2") (pintype "passive"))
      (node (ref "C14") (pin "2") (pinfunction "2_2") (pintype "passive"))
      (node (ref "C15") (pin "2") (pinfunction "2_2") (pintype "passive"))
      (node (ref "SW2") (pin "2") (pinfunction "2_2") (pintype "passive"))
      (node (ref "U1") (pin "8") (pinfunction "VOUT_8") (pintype "passive"))
    )
    (net (code "55") (name "Net-(U7-RST#)") (class "Default")
      (node (ref "R9") (pin "2") (pinfunction "2_2") (pintype "passive"))
      (node (ref "U7") (pin "9") (pinfunction "RST#_9") (pintype "passive"))
    )
    (net (code "56") (name "Net-(U7-RXD)") (class "Default")
      (node (ref "R10") (pin "1") (pinfunction "1_1") (pintype "passive"))
      (node (ref "U7") (pin "25") (pinfunction "RXD_25") (pintype "passive"))
    )
    (net (code "57") (name "Net-(U7-TXD)") (class "Default")
      (node (ref "R11") (pin "1") (pinfunction "1_1") (pintype "passive"))
      (node (ref "U7") (pin "26") (pinfunction "TXD_26") (pintype "passive"))
    )
    (net (code "58") (name "VBUS") (class "Default")
      (node (ref "D2") (pin "2") (pinfunction "K_2") (pintype "passive"))
      (node (ref "TYPE-C1") (pin "A4") (pinfunction "VBUS_A4") (pintype "passive"))
      (node (ref "TYPE-C1") (pin "A9") (pinfunction "VBUS_A9") (pintype "passive"))
      (node (ref "TYPE-C1") (pin "B4") (pinfunction "VBUS_B4") (pintype "passive"))
      (node (ref "TYPE-C1") (pin "B9") (pinfunction "VBUS_B9") (pintype "passive"))
    )
    (net (code "59") (name "VCCBAT") (class "Default")
      (node (ref "C16") (pin "2") (pinfunction "2_2") (pintype "passive"))
      (node (ref "L2") (pin "2") (pinfunction "2_2") (pintype "passive"))
      (node (ref "R7") (pin "2") (pinfunction "2_2") (pintype "passive"))
      (node (ref "电池接口1") (pin "1") (pinfunction "1_1") (pintype "passive"))
    )
    (net (code "60") (name "VIN") (class "Default")
      (node (ref "C18") (pin "2") (pinfunction "2_2") (pintype "passive"))
      (node (ref "GA6-B模块") (pin "4") (pinfunction "4_4") (pintype "passive"))
      (node (ref "HC-SR04超声波测距") (pin "1") (pinfunction "1_1") (pintype "passive"))
      (node (ref "MH-Z19B_CO2传感器") (pin "4") (pinfunction "4_4") (pintype "passive"))
      (node (ref "SW2") (pin "1") (pinfunction "1_1") (pintype "passive"))
      (node (ref "U3") (pin "3") (pinfunction "VIN_3") (pintype "passive"))
    )
    (net (code "61") (name "unconnected-(CN1-Pad1)") (class "Default")
      (node (ref "CN1") (pin "1") (pinfunction "1_1") (pintype "passive"))
    )
    (net (code "62") (name "unconnected-(CN1-Pad2)") (class "Default")
      (node (ref "CN1") (pin "2") (pinfunction "2_2") (pintype "passive"))
    )
    (net (code "63") (name "unconnected-(CN2-Pad1)") (class "Default")
      (node (ref "CN2") (pin "1") (pinfunction "1_1") (pintype "passive"))
    )
    (net (code "64") (name "unconnected-(CN2-Pad2)") (class "Default")
      (node (ref "CN2") (pin "2") (pinfunction "2_2") (pintype "passive"))
    )
    (net (code "65") (name "unconnected-(CN2-Pad3)") (class "Default")
      (node (ref "CN2") (pin "3") (pinfunction "3_3") (pintype "passive"))
    )
    (net (code "66") (name "unconnected-(CN2-Pad4)") (class "Default")
      (node (ref "CN2") (pin "4") (pinfunction "4_4") (pintype "passive"))
    )
    (net (code "67") (name "unconnected-(CN3-Pad1)") (class "Default")
      (node (ref "CN3") (pin "1") (pinfunction "1_1") (pintype "passive"))
    )
    (net (code "68") (name "unconnected-(CN3-Pad2)") (class "Default")
      (node (ref "CN3") (pin "2") (pinfunction "2_2") (pintype "passive"))
    )
    (net (code "69") (name "unconnected-(CN3-Pad3)") (class "Default")
      (node (ref "CN3") (pin "3") (pinfunction "3_3") (pintype "passive"))
    )
    (net (code "70") (name "unconnected-(LED2-DOUT-Pad2)") (class "Default")
      (node (ref "LED2") (pin "2") (pinfunction "DOUT_2") (pintype "passive"))
    )
    (net (code "71") (name "unconnected-(MH-Z19B_CO2传感器-Pad2)") (class "Default")
      (node (ref "MH-Z19B_CO2传感器") (pin "2") (pinfunction "2_2") (pintype "passive"))
    )
    (net (code "72") (name "unconnected-(SW1-Pad1)") (class "Default")
      (node (ref "SW1") (pin "1") (pinfunction "1_1") (pintype "passive"))
    )
    (net (code "73") (name "unconnected-(SW1-Pad2)") (class "Default")
      (node (ref "SW1") (pin "2") (pinfunction "2_2") (pintype "passive"))
    )
    (net (code "74") (name "unconnected-(SW2-Pad3)") (class "Default")
      (node (ref "SW2") (pin "3") (pinfunction "3_3") (pintype "passive"))
    )
    (net (code "75") (name "unconnected-(SW2-Pad4)") (class "Default")
      (node (ref "SW2") (pin "4") (pinfunction "4_4") (pintype "passive"))
    )
    (net (code "76") (name "unconnected-(SW2-Pad5)") (class "Default")
      (node (ref "SW2") (pin "5") (pinfunction "5_5") (pintype "passive"))
    )
    (net (code "77") (name "unconnected-(TP1-Pad1)") (class "Default")
      (node (ref "TP1") (pin "1") (pinfunction "1_1") (pintype "passive"))
    )
    (net (code "78") (name "unconnected-(TP2-Pad1)") (class "Default")
      (node (ref "TP2") (pin "1") (pinfunction "1_1") (pintype "passive"))
    )
    (net (code "79") (name "unconnected-(TP3-Pad1)") (class "Default")
      (node (ref "TP3") (pin "1") (pinfunction "1_1") (pintype "passive"))
    )
    (net (code "80") (name "unconnected-(TP4-Pad1)") (class "Default")
      (node (ref "TP4") (pin "1") (pinfunction "1_1") (pintype "passive"))
    )
    (net (code "81") (name "unconnected-(TYPE-C1-CC1-PadA5)") (class "Default")
      (node (ref "TYPE-C1") (pin "A5") (pinfunction "CC1_A5") (pintype "passive"))
    )
    (net (code "82") (name "unconnected-(TYPE-C1-CC2-PadB5)") (class "Default")
      (node (ref "TYPE-C1") (pin "B5") (pinfunction "CC2_B5") (pintype "passive"))
    )
    (net (code "83") (name "unconnected-(TYPE-C1-SUB1-PadA8)") (class "Default")
      (node (ref "TYPE-C1") (pin "A8") (pinfunction "SUB1_A8") (pintype "passive"))
    )
    (net (code "84") (name "unconnected-(TYPE-C1-SUB2-PadB8)") (class "Default")
      (node (ref "TYPE-C1") (pin "B8") (pinfunction "SUB2_B8") (pintype "passive"))
    )
    (net (code "85") (name "unconnected-(U7-CTS-Pad23)") (class "Default")
      (node (ref "U7") (pin "23") (pinfunction "CTS_23") (pintype "passive"))
    )
    (net (code "86") (name "unconnected-(U7-DCD-Pad1)") (class "Default")
      (node (ref "U7") (pin "1") (pinfunction "DCD_1") (pintype "passive"))
    )
    (net (code "87") (name "unconnected-(U7-DSR-Pad27)") (class "Default")
      (node (ref "U7") (pin "27") (pinfunction "DSR_27") (pintype "passive"))
    )
    (net (code "88") (name "unconnected-(U7-EP-Pad29)") (class "Default")
      (node (ref "U7") (pin "29") (pinfunction "EP_29") (pintype "passive"))
    )
    (net (code "89") (name "unconnected-(U7-NC-Pad10)") (class "Default")
      (node (ref "U7") (pin "10") (pinfunction "NC_10") (pintype "passive"))
    )
    (net (code "90") (name "unconnected-(U7-NC-Pad13)") (class "Default")
      (node (ref "U7") (pin "13") (pinfunction "NC_13") (pintype "passive"))
    )
    (net (code "91") (name "unconnected-(U7-NC-Pad14)") (class "Default")
      (node (ref "U7") (pin "14") (pinfunction "NC_14") (pintype "passive"))
    )
    (net (code "92") (name "unconnected-(U7-NC-Pad15)") (class "Default")
      (node (ref "U7") (pin "15") (pinfunction "NC_15") (pintype "passive"))
    )
    (net (code "93") (name "unconnected-(U7-NC-Pad16)") (class "Default")
      (node (ref "U7") (pin "16") (pinfunction "NC_16") (pintype "passive"))
    )
    (net (code "94") (name "unconnected-(U7-NC-Pad17)") (class "Default")
      (node (ref "U7") (pin "17") (pinfunction "NC_17") (pintype "passive"))
    )
    (net (code "95") (name "unconnected-(U7-NC-Pad18)") (class "Default")
      (node (ref "U7") (pin "18") (pinfunction "NC_18") (pintype "passive"))
    )
    (net (code "96") (name "unconnected-(U7-NC-Pad19)") (class "Default")
      (node (ref "U7") (pin "19") (pinfunction "NC_19") (pintype "passive"))
    )
    (net (code "97") (name "unconnected-(U7-NC-Pad20)") (class "Default")
      (node (ref "U7") (pin "20") (pinfunction "NC_20") (pintype "passive"))
    )
    (net (code "98") (name "unconnected-(U7-NC-Pad21)") (class "Default")
      (node (ref "U7") (pin "21") (pinfunction "NC_21") (pintype "passive"))
    )
    (net (code "99") (name "unconnected-(U7-NC-Pad22)") (class "Default")
      (node (ref "U7") (pin "22") (pinfunction "NC_22") (pintype "passive"))
    )
    (net (code "100") (name "unconnected-(U7-RI-Pad2)") (class "Default")
      (node (ref "U7") (pin "2") (pinfunction "RI_2") (pintype "passive"))
    )
    (net (code "101") (name "unconnected-(U7-SUSPEND#-Pad11)") (class "Default")
      (node (ref "U7") (pin "11") (pinfunction "SUSPEND#_11") (pintype "passive"))
    )
    (net (code "102") (name "unconnected-(U7-SUSPEND-Pad12)") (class "Default")
      (node (ref "U7") (pin "12") (pinfunction "SUSPEND_12") (pintype "passive"))
    )
    (net (code "103") (name "unconnected-(U8-NC-Pad32)") (class "Default")
      (node (ref "U8") (pin "32") (pinfunction "NC_32") (pintype "passive"))
    )
  )
)
